# Environmental_Module.net
KiCad netlist of a schematic drawn in EAGLE
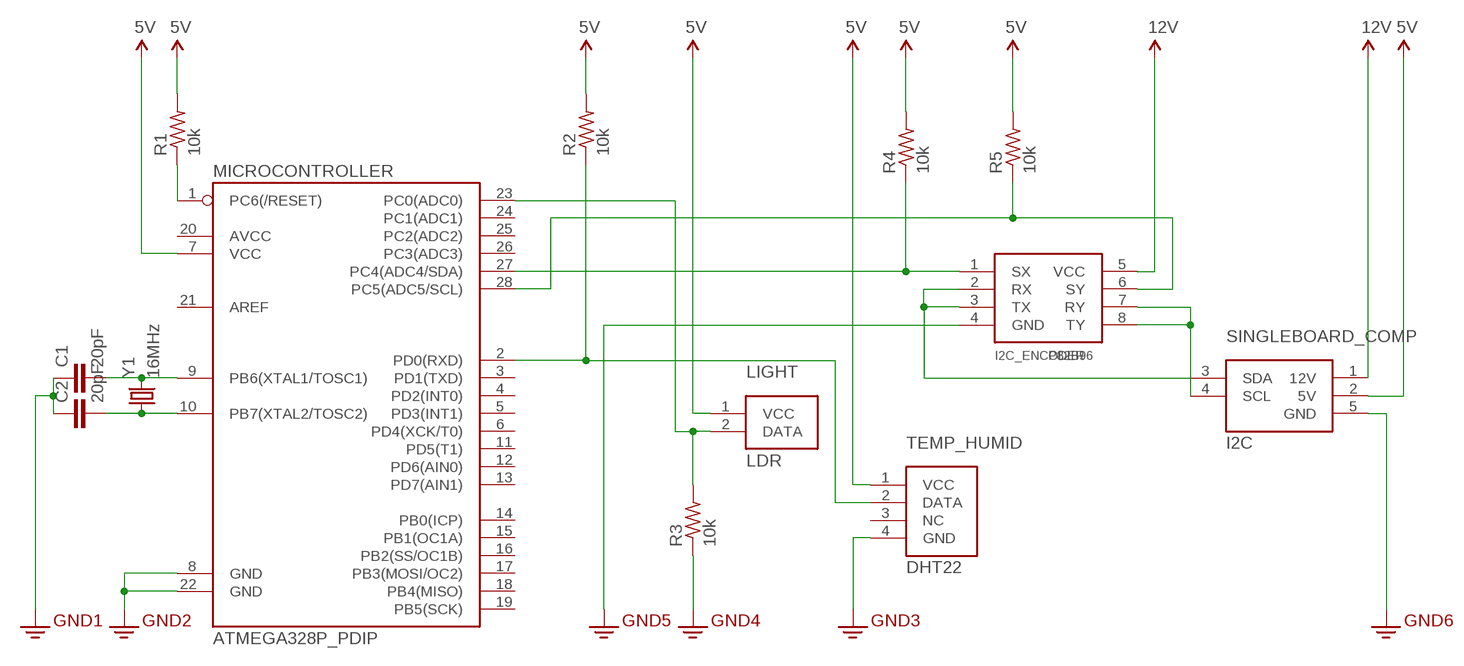
[diagram p0: schematic, sheet 1]

(export (version "E")
  (design (tool "Eeschema 10.0.6"))
  (components
    (comp (ref "C1")
      (value "20pF")
      (footprint "eagle-import:CAP-PTH-SMALL")
      (libsource (lib "eagle-import") (part "CAPPTH"))
    )
    (comp (ref "C2")
      (value "20pF")
      (footprint "eagle-import:CAP-PTH-SMALL")
      (libsource (lib "eagle-import") (part "CAPPTH"))
    )
    (comp (ref "I2C_ENCODER")
      (value "P82B96")
      (footprint "eagle-import:DIP08")
      (libsource (lib "eagle-import") (part "P82B96"))
    )
    (comp (ref "LIGHT")
      (value "LDR")
      (footprint "eagle-import:LDR")
      (libsource (lib "eagle-import") (part "LDR"))
    )
    (comp (ref "MICROCONTROLLER")
      (value "ATMEGA328P_PDIP")
      (footprint "eagle-import:DIL28-3")
      (libsource (lib "eagle-import") (part "ATMEGA328P_PDIP"))
    )
    (comp (ref "R1")
      (value "10k")
      (footprint "eagle-import:0204_7")
      (libsource (lib "eagle-import") (part "R-US_0204/7"))
    )
    (comp (ref "R2")
      (value "10k")
      (footprint "eagle-import:0204_7")
      (libsource (lib "eagle-import") (part "R-US_0204/7"))
    )
    (comp (ref "R3")
      (value "10k")
      (footprint "eagle-import:0204_7")
      (libsource (lib "eagle-import") (part "R-US_0204/7"))
    )
    (comp (ref "R4")
      (value "10k")
      (footprint "eagle-import:0204_7")
      (libsource (lib "eagle-import") (part "R-US_0204/7"))
    )
    (comp (ref "R5")
      (value "10k")
      (footprint "eagle-import:0204_7")
      (libsource (lib "eagle-import") (part "R-US_0204/7"))
    )
    (comp (ref "SINGLEBOARD_COMP")
      (value "I2C")
      (footprint "eagle-import:I2C_TERM")
      (libsource (lib "eagle-import") (part "I2C"))
    )
    (comp (ref "TEMP_HUMID")
      (value "DHT22")
      (footprint "eagle-import:DHT22")
      (libsource (lib "eagle-import") (part "DHT22"))
    )
    (comp (ref "Y1")
      (value "16MHz")
      (footprint "eagle-import:HC49US")
      (libsource (lib "eagle-import") (part "CRYSTALHC49US"))
    )
  )
  (nets
    (net (code "1") (name "5V") (class "Default")
      (node (ref "LIGHT") (pin "1") (pinfunction "VCC_1") (pintype "bidirectional"))
      (node (ref "MICROCONTROLLER") (pin "7") (pinfunction "VCC_7") (pintype "bidirectional"))
      (node (ref "R1") (pin "2") (pinfunction "2_2") (pintype "passive"))
      (node (ref "R2") (pin "2") (pinfunction "2_2") (pintype "passive"))
      (node (ref "R4") (pin "2") (pinfunction "2_2") (pintype "passive"))
      (node (ref "R5") (pin "2") (pinfunction "2_2") (pintype "passive"))
      (node (ref "SINGLEBOARD_COMP") (pin "2") (pinfunction "5V_2") (pintype "bidirectional"))
      (node (ref "TEMP_HUMID") (pin "1") (pinfunction "VCC_1") (pintype "bidirectional"))
    )
    (net (code "2") (name "12V") (class "Default")
      (node (ref "I2C_ENCODER") (pin "5") (pinfunction "VCC_5") (pintype "bidirectional"))
      (node (ref "SINGLEBOARD_COMP") (pin "1") (pinfunction "12V_1") (pintype "bidirectional"))
    )
    (net (code "3") (name "GND2") (class "Default")
      (node (ref "C1") (pin "1") (pinfunction "1_1") (pintype "passive"))
      (node (ref "C2") (pin "1") (pinfunction "1_1") (pintype "passive"))
      (node (ref "I2C_ENCODER") (pin "4") (pinfunction "GND_4") (pintype "bidirectional"))
      (node (ref "MICROCONTROLLER") (pin "22") (pinfunction "GND_22") (pintype "bidirectional"))
      (node (ref "MICROCONTROLLER") (pin "8") (pinfunction "GND_8") (pintype "bidirectional"))
      (node (ref "R3") (pin "1") (pinfunction "1_1") (pintype "passive"))
      (node (ref "SINGLEBOARD_COMP") (pin "5") (pinfunction "GND_5") (pintype "bidirectional"))
      (node (ref "TEMP_HUMID") (pin "4") (pinfunction "GND_4") (pintype "bidirectional"))
    )
    (net (code "4") (name "Net-(I2C_ENCODER-RX)") (class "Default")
      (node (ref "I2C_ENCODER") (pin "2") (pinfunction "RX_2") (pintype "bidirectional"))
      (node (ref "I2C_ENCODER") (pin "3") (pinfunction "TX_3") (pintype "bidirectional"))
      (node (ref "SINGLEBOARD_COMP") (pin "3") (pinfunction "SDA_3") (pintype "bidirectional"))
    )
    (net (code "5") (name "Net-(I2C_ENCODER-RY)") (class "Default")
      (node (ref "I2C_ENCODER") (pin "7") (pinfunction "RY_7") (pintype "bidirectional"))
      (node (ref "I2C_ENCODER") (pin "8") (pinfunction "TY_8") (pintype "bidirectional"))
      (node (ref "SINGLEBOARD_COMP") (pin "4") (pinfunction "SCL_4") (pintype "bidirectional"))
    )
    (net (code "6") (name "Net-(I2C_ENCODER-SX)") (class "Default")
      (node (ref "I2C_ENCODER") (pin "1") (pinfunction "SX_1") (pintype "bidirectional"))
      (node (ref "MICROCONTROLLER") (pin "27") (pinfunction "PC4(ADC4/SDA)_27") (pintype "bidirectional"))
      (node (ref "R4") (pin "1") (pinfunction "1_1") (pintype "passive"))
    )
    (net (code "7") (name "Net-(I2C_ENCODER-SY)") (class "Default")
      (node (ref "I2C_ENCODER") (pin "6") (pinfunction "SY_6") (pintype "bidirectional"))
      (node (ref "MICROCONTROLLER") (pin "28") (pinfunction "PC5(ADC5/SCL)_28") (pintype "bidirectional"))
      (node (ref "R5") (pin "1") (pinfunction "1_1") (pintype "passive"))
    )
    (net (code "8") (name "Net-(LIGHT-DATA)") (class "Default")
      (node (ref "LIGHT") (pin "2") (pinfunction "DATA_2") (pintype "bidirectional"))
      (node (ref "MICROCONTROLLER") (pin "23") (pinfunction "PC0(ADC0)_23") (pintype "bidirectional"))
      (node (ref "R3") (pin "2") (pinfunction "2_2") (pintype "passive"))
    )
    (net (code "9") (name "Net-(MICROCONTROLLER-PB6(XTAL1{slash}TOSC1))") (class "Default")
      (node (ref "C1") (pin "2") (pinfunction "2_2") (pintype "passive"))
      (node (ref "MICROCONTROLLER") (pin "9") (pinfunction "PB6(XTAL1/TOSC1)_9") (pintype "bidirectional"))
      (node (ref "Y1") (pin "2") (pinfunction "2_2") (pintype "passive"))
    )
    (net (code "10") (name "Net-(MICROCONTROLLER-PB7(XTAL2{slash}TOSC2))") (class "Default")
      (node (ref "C2") (pin "2") (pinfunction "2_2") (pintype "passive"))
      (node (ref "MICROCONTROLLER") (pin "10") (pinfunction "PB7(XTAL2/TOSC2)_10") (pintype "bidirectional"))
      (node (ref "Y1") (pin "1") (pinfunction "1_1") (pintype "passive"))
    )
    (net (code "11") (name "Net-(MICROCONTROLLER-PC6({slash}RESET))") (class "Default")
      (node (ref "MICROCONTROLLER") (pin "1") (pinfunction "PC6(/RESET)_1") (pintype "bidirectional"))
      (node (ref "R1") (pin "1") (pinfunction "1_1") (pintype "passive"))
    )
    (net (code "12") (name "Net-(MICROCONTROLLER-PD0(RXD))") (class "Default")
      (node (ref "MICROCONTROLLER") (pin "2") (pinfunction "PD0(RXD)_2") (pintype "bidirectional"))
      (node (ref "R2") (pin "1") (pinfunction "1_1") (pintype "passive"))
      (node (ref "TEMP_HUMID") (pin "2") (pinfunction "DATA_2") (pintype "bidirectional"))
    )
    (net (code "13") (name "unconnected-(MICROCONTROLLER-AREF-Pad21)") (class "Default")
      (node (ref "MICROCONTROLLER") (pin "21") (pinfunction "AREF_21") (pintype "bidirectional"))
    )
    (net (code "14") (name "unconnected-(MICROCONTROLLER-AVCC-Pad20)") (class "Default")
      (node (ref "MICROCONTROLLER") (pin "20") (pinfunction "AVCC_20") (pintype "bidirectional"))
    )
    (net (code "15") (name "unconnected-(MICROCONTROLLER-PB0(ICP)-Pad14)") (class "Default")
      (node (ref "MICROCONTROLLER") (pin "14") (pinfunction "PB0(ICP)_14") (pintype "bidirectional"))
    )
    (net (code "16") (name "unconnected-(MICROCONTROLLER-PB1(OC1A)-Pad15)") (class "Default")
      (node (ref "MICROCONTROLLER") (pin "15") (pinfunction "PB1(OC1A)_15") (pintype "bidirectional"))
    )
    (net (code "17") (name "unconnected-(MICROCONTROLLER-PB2(SS{slash}OC1B)-Pad16)") (class "Default")
      (node (ref "MICROCONTROLLER") (pin "16") (pinfunction "PB2(SS/OC1B)_16") (pintype "bidirectional"))
    )
    (net (code "18") (name "unconnected-(MICROCONTROLLER-PB3(MOSI{slash}OC2)-Pad17)") (class "Default")
      (node (ref "MICROCONTROLLER") (pin "17") (pinfunction "PB3(MOSI/OC2)_17") (pintype "bidirectional"))
    )
    (net (code "19") (name "unconnected-(MICROCONTROLLER-PB4(MISO)-Pad18)") (class "Default")
      (node (ref "MICROCONTROLLER") (pin "18") (pinfunction "PB4(MISO)_18") (pintype "bidirectional"))
    )
    (net (code "20") (name "unconnected-(MICROCONTROLLER-PB5(SCK)-Pad19)") (class "Default")
      (node (ref "MICROCONTROLLER") (pin "19") (pinfunction "PB5(SCK)_19") (pintype "bidirectional"))
    )
    (net (code "21") (name "unconnected-(MICROCONTROLLER-PC1(ADC1)-Pad24)") (class "Default")
      (node (ref "MICROCONTROLLER") (pin "24") (pinfunction "PC1(ADC1)_24") (pintype "bidirectional"))
    )
    (net (code "22") (name "unconnected-(MICROCONTROLLER-PC2(ADC2)-Pad25)") (class "Default")
      (node (ref "MICROCONTROLLER") (pin "25") (pinfunction "PC2(ADC2)_25") (pintype "bidirectional"))
    )
    (net (code "23") (name "unconnected-(MICROCONTROLLER-PC3(ADC3)-Pad26)") (class "Default")
      (node (ref "MICROCONTROLLER") (pin "26") (pinfunction "PC3(ADC3)_26") (pintype "bidirectional"))
    )
    (net (code "24") (name "unconnected-(MICROCONTROLLER-PD1(TXD)-Pad3)") (class "Default")
      (node (ref "MICROCONTROLLER") (pin "3") (pinfunction "PD1(TXD)_3") (pintype "bidirectional"))
    )
    (net (code "25") (name "unconnected-(MICROCONTROLLER-PD2(INT0)-Pad4)") (class "Default")
      (node (ref "MICROCONTROLLER") (pin "4") (pinfunction "PD2(INT0)_4") (pintype "bidirectional"))
    )
    (net (code "26") (name "unconnected-(MICROCONTROLLER-PD3(INT1)-Pad5)") (class "Default")
      (node (ref "MICROCONTROLLER") (pin "5") (pinfunction "PD3(INT1)_5") (pintype "bidirectional"))
    )
    (net (code "27") (name "unconnected-(MICROCONTROLLER-PD4(XCK{slash}T0)-Pad6)") (class "Default")
      (node (ref "MICROCONTROLLER") (pin "6") (pinfunction "PD4(XCK/T0)_6") (pintype "bidirectional"))
    )
    (net (code "28") (name "unconnected-(MICROCONTROLLER-PD5(T1)-Pad11)") (class "Default")
      (node (ref "MICROCONTROLLER") (pin "11") (pinfunction "PD5(T1)_11") (pintype "bidirectional"))
    )
    (net (code "29") (name "unconnected-(MICROCONTROLLER-PD6(AIN0)-Pad12)") (class "Default")
      (node (ref "MICROCONTROLLER") (pin "12") (pinfunction "PD6(AIN0)_12") (pintype "bidirectional"))
    )
    (net (code "30") (name "unconnected-(MICROCONTROLLER-PD7(AIN1)-Pad13)") (class "Default")
      (node (ref "MICROCONTROLLER") (pin "13") (pinfunction "PD7(AIN1)_13") (pintype "bidirectional"))
    )
    (net (code "31") (name "unconnected-(TEMP_HUMID-NC-Pad3)") (class "Default")
      (node (ref "TEMP_HUMID") (pin "3") (pinfunction "NC_3") (pintype "bidirectional"))
    )
  )
)
